# mod_mixer_v0_3_1.net
KiCad netlist of a schematic drawn in EAGLE
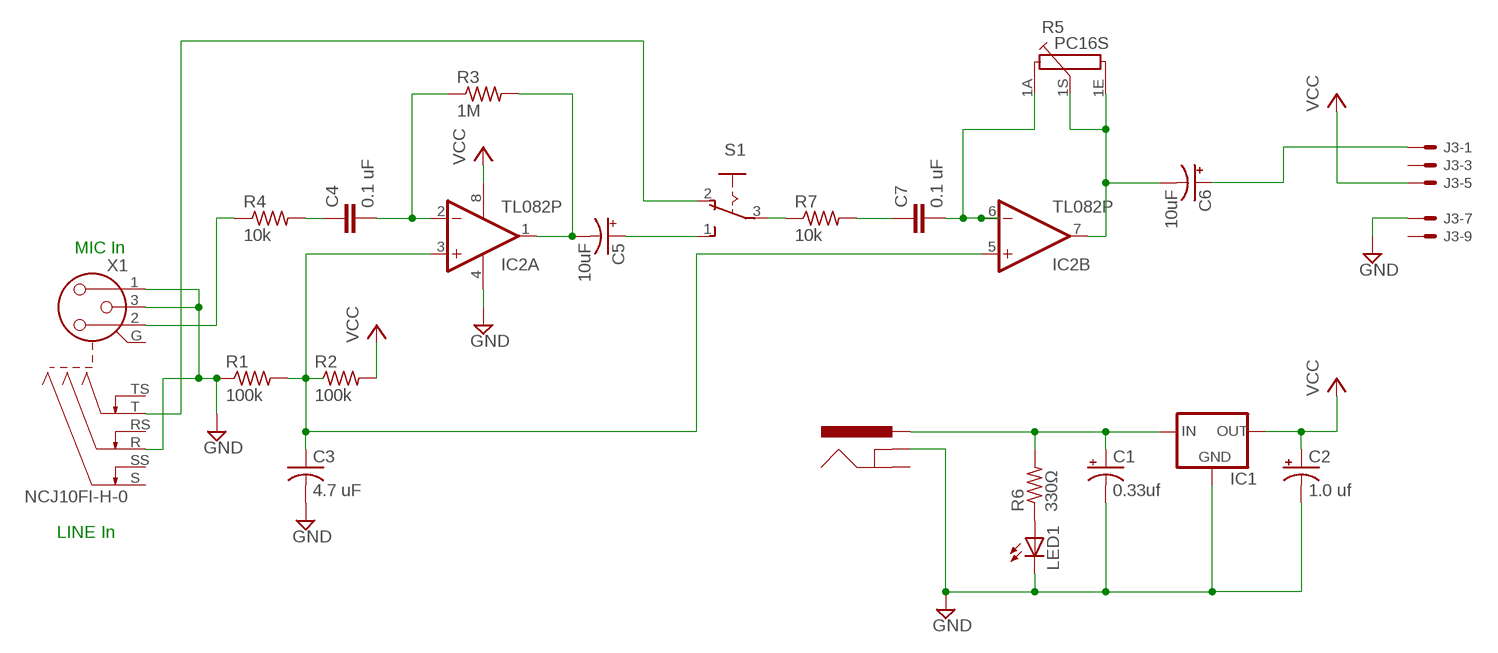
[diagram p0: schematic, sheet 1]

(export (version "E")
  (design (tool "Eeschema 10.0.6"))
  (components
    (comp (ref "C1")
      (value "0.33uf")
      (footprint "eagle-import:E2,5-6")
      (libsource (lib "eagle-import") (part "CPOL-USE2.5-6"))
    )
    (comp (ref "C2")
      (value "1.0 uf")
      (footprint "eagle-import:E2,5-6")
      (libsource (lib "eagle-import") (part "CPOL-USE2.5-6"))
    )
    (comp (ref "C3")
      (value "4.7 uF")
      (footprint "eagle-import:C050-030X075")
      (libsource (lib "eagle-import") (part "C-US050-030X075"))
    )
    (comp (ref "C4")
      (value "0.1 uF")
      (footprint "eagle-import:C5B2.5")
      (libsource (lib "eagle-import") (part "C5/2.5"))
    )
    (comp (ref "C5")
      (value "10uF")
      (footprint "eagle-import:E5-6")
      (libsource (lib "eagle-import") (part "CPOL-USE5-6"))
    )
    (comp (ref "C6")
      (value "10uF")
      (footprint "eagle-import:E2,5-7")
      (libsource (lib "eagle-import") (part "CPOL-USE2.5-7"))
    )
    (comp (ref "C7")
      (value "0.1 uF")
      (footprint "eagle-import:C5B2.5")
      (libsource (lib "eagle-import") (part "C5/2.5"))
    )
    (comp (ref "IC1")
      (value "V_REG_78XXSIDE")
      (footprint "eagle-import:78XXL")
      (libsource (lib "eagle-import") (part "V_REG_78XXSIDE"))
    )
    (comp (ref "IC2")
      (value "TL082P")
      (footprint "eagle-import:DIL08")
      (libsource (lib "eagle-import") (part "TL082P"))
    )
    (comp (ref "J1")
      (value "POWER_JACKSLT")
      (footprint "eagle-import:POWER_JACK_SLOT")
      (libsource (lib "eagle-import") (part "POWER_JACKSLT"))
    )
    (comp (ref "J3")
      (value "CON-50-EDGE")
      (footprint "eagle-import:CARDEDGE-50")
      (libsource (lib "eagle-import") (part "CON-50-EDGE"))
    )
    (comp (ref "LED1")
      (value "LEDSFH480")
      (footprint "eagle-import:SFH480")
      (libsource (lib "eagle-import") (part "LEDSFH480"))
    )
    (comp (ref "R1")
      (value "100k")
      (footprint "eagle-import:0207_10")
      (libsource (lib "eagle-import") (part "R-US_0207/10"))
    )
    (comp (ref "R2")
      (value "100k")
      (footprint "eagle-import:0207_10")
      (libsource (lib "eagle-import") (part "R-US_0207/10"))
    )
    (comp (ref "R3")
      (value "1M")
      (footprint "eagle-import:0207_10")
      (libsource (lib "eagle-import") (part "R-US_0207/10"))
    )
    (comp (ref "R4")
      (value "10k")
      (footprint "eagle-import:0207_10")
      (libsource (lib "eagle-import") (part "R-US_0207/10"))
    )
    (comp (ref "R5")
      (value "PC16S")
      (footprint "eagle-import:PC16S")
      (libsource (lib "eagle-import") (part "PC16S"))
    )
    (comp (ref "R6")
      (value "330Ω")
      (footprint "eagle-import:0207_10")
      (libsource (lib "eagle-import") (part "R-US_0207/10"))
    )
    (comp (ref "R7")
      (value "10k")
      (footprint "eagle-import:0207_10")
      (libsource (lib "eagle-import") (part "R-US_0207/10"))
    )
    (comp (ref "S1")
      (value "255SB")
      (footprint "eagle-import:255SB")
      (libsource (lib "eagle-import") (part "255SB"))
    )
    (comp (ref "X1")
      (value "NCJ10FI-H-0")
      (footprint "eagle-import:NCJ10FI-H-0")
      (libsource (lib "eagle-import") (part "NCJ10FI-H-0"))
    )
  )
  (nets
    (net (code "1") (name "GND") (class "Default")
      (node (ref "C1") (pin "-") (pinfunction "-_-") (pintype "passive"))
      (node (ref "C2") (pin "-") (pinfunction "-_-") (pintype "passive"))
      (node (ref "C3") (pin "2") (pinfunction "2_2") (pintype "passive"))
      (node (ref "IC1") (pin "GND") (pinfunction "GND_GND") (pintype "input"))
      (node (ref "IC2") (pin "4") (pinfunction "V-_4") (pintype "power_in"))
      (node (ref "J1") (pin "GND@1") (pinfunction "GNDBREAK_GND@1") (pintype "bidirectional"))
      (node (ref "J3") (pin "7") (pinfunction "S_7") (pintype "passive"))
      (node (ref "LED1") (pin "K") (pinfunction "C_K") (pintype "passive"))
      (node (ref "R1") (pin "1") (pinfunction "1_1") (pintype "passive"))
      (node (ref "X1") (pin "1") (pinfunction "1_1") (pintype "passive"))
      (node (ref "X1") (pin "3") (pinfunction "3_3") (pintype "passive"))
      (node (ref "X1") (pin "R") (pinfunction "R_R") (pintype "passive"))
    )
    (net (code "2") (name "Net-(C1-Pad+)") (class "Default")
      (node (ref "C1") (pin "+") (pinfunction "+_+") (pintype "passive"))
      (node (ref "IC1") (pin "IN") (pinfunction "IN_IN") (pintype "input"))
      (node (ref "J1") (pin "PWR") (pinfunction "PWR_PWR") (pintype "bidirectional"))
      (node (ref "R6") (pin "2") (pinfunction "2_2") (pintype "passive"))
    )
    (net (code "3") (name "Net-(C4-Pad1)") (class "Default")
      (node (ref "C4") (pin "1") (pinfunction "1_1") (pintype "passive"))
      (node (ref "R4") (pin "2") (pinfunction "2_2") (pintype "passive"))
    )
    (net (code "4") (name "Net-(C7-Pad1)") (class "Default")
      (node (ref "C7") (pin "1") (pinfunction "1_1") (pintype "passive"))
      (node (ref "R7") (pin "2") (pinfunction "2_2") (pintype "passive"))
    )
    (net (code "5") (name "Net-(IC2A-+IN)") (class "Default")
      (node (ref "C3") (pin "1") (pinfunction "1_1") (pintype "passive"))
      (node (ref "IC2") (pin "3") (pinfunction "+IN_3") (pintype "input"))
      (node (ref "IC2") (pin "5") (pinfunction "+IN_5") (pintype "input"))
      (node (ref "R1") (pin "2") (pinfunction "2_2") (pintype "passive"))
      (node (ref "R2") (pin "1") (pinfunction "1_1") (pintype "passive"))
    )
    (net (code "6") (name "Net-(IC2A--IN)") (class "Default")
      (node (ref "C4") (pin "2") (pinfunction "2_2") (pintype "passive"))
      (node (ref "IC2") (pin "2") (pinfunction "-IN_2") (pintype "input"))
      (node (ref "R3") (pin "1") (pinfunction "1_1") (pintype "passive"))
    )
    (net (code "7") (name "Net-(IC2A-OUT)") (class "Default")
      (node (ref "C5") (pin "-") (pinfunction "-_-") (pintype "passive"))
      (node (ref "IC2") (pin "1") (pinfunction "OUT_1") (pintype "output"))
      (node (ref "R3") (pin "2") (pinfunction "2_2") (pintype "passive"))
    )
    (net (code "8") (name "Net-(IC2B--IN)") (class "Default")
      (node (ref "C7") (pin "2") (pinfunction "2_2") (pintype "passive"))
      (node (ref "IC2") (pin "6") (pinfunction "-IN_6") (pintype "input"))
      (node (ref "R5") (pin "1A") (pinfunction "1A_1A") (pintype "passive"))
    )
    (net (code "9") (name "Net-(IC2B-OUT)") (class "Default")
      (node (ref "C6") (pin "-") (pinfunction "-_-") (pintype "passive"))
      (node (ref "IC2") (pin "7") (pinfunction "OUT_7") (pintype "output"))
      (node (ref "R5") (pin "1E") (pinfunction "1E_1E") (pintype "passive"))
      (node (ref "R5") (pin "1S") (pinfunction "1S_1S") (pintype "passive"))
    )
    (net (code "10") (name "Net-(J3A-S)") (class "Default")
      (node (ref "C6") (pin "+") (pinfunction "+_+") (pintype "passive"))
      (node (ref "J3") (pin "1") (pinfunction "S_1") (pintype "passive"))
    )
    (net (code "11") (name "Net-(LED1-PadA)") (class "Default")
      (node (ref "LED1") (pin "A") (pinfunction "A_A") (pintype "passive"))
      (node (ref "R6") (pin "1") (pinfunction "1_1") (pintype "passive"))
    )
    (net (code "12") (name "Net-(R4-Pad1)") (class "Default")
      (node (ref "R4") (pin "1") (pinfunction "1_1") (pintype "passive"))
      (node (ref "X1") (pin "2") (pinfunction "2_2") (pintype "passive"))
    )
    (net (code "13") (name "Net-(S1-O)") (class "Default")
      (node (ref "S1") (pin "2") (pinfunction "O_2") (pintype "passive"))
      (node (ref "X1") (pin "T") (pinfunction "T_T") (pintype "passive"))
    )
    (net (code "14") (name "Net-(S1-P)") (class "Default")
      (node (ref "R7") (pin "1") (pinfunction "1_1") (pintype "passive"))
      (node (ref "S1") (pin "3") (pinfunction "P_3") (pintype "passive"))
    )
    (net (code "15") (name "Net-(S1-S)") (class "Default")
      (node (ref "C5") (pin "+") (pinfunction "+_+") (pintype "passive"))
      (node (ref "S1") (pin "1") (pinfunction "S_1") (pintype "passive"))
    )
    (net (code "16") (name "VCC") (class "Default")
      (node (ref "C2") (pin "+") (pinfunction "+_+") (pintype "passive"))
      (node (ref "IC1") (pin "OUT") (pinfunction "OUT_OUT") (pintype "output"))
      (node (ref "IC2") (pin "8") (pinfunction "V+_8") (pintype "power_in"))
      (node (ref "J3") (pin "5") (pinfunction "S_5") (pintype "passive"))
      (node (ref "R2") (pin "2") (pinfunction "2_2") (pintype "passive"))
    )
    (net (code "17") (name "unconnected-(J1-GND-PadGND@2)") (class "Default")
      (node (ref "J1") (pin "GND@2") (pinfunction "GND_GND@2") (pintype "bidirectional"))
    )
    (net (code "18") (name "unconnected-(J3B-S-Pad3)") (class "Default")
      (node (ref "J3") (pin "3") (pinfunction "S_3") (pintype "passive"))
    )
    (net (code "19") (name "unconnected-(J3E-S-Pad9)") (class "Default")
      (node (ref "J3") (pin "9") (pinfunction "S_9") (pintype "passive"))
    )
    (net (code "20") (name "unconnected-(X1-PadG)") (class "Default")
      (node (ref "X1") (pin "G") (pinfunction "G_G") (pintype "passive"))
    )
    (net (code "21") (name "unconnected-(X1-PadRS)") (class "Default")
      (node (ref "X1") (pin "RS") (pinfunction "RS_RS") (pintype "passive"))
    )
    (net (code "22") (name "unconnected-(X1-PadS)") (class "Default")
      (node (ref "X1") (pin "S") (pinfunction "S_S") (pintype "passive"))
    )
    (net (code "23") (name "unconnected-(X1-PadSS)") (class "Default")
      (node (ref "X1") (pin "SS") (pinfunction "SS_SS") (pintype "passive"))
    )
    (net (code "24") (name "unconnected-(X1-PadTS)") (class "Default")
      (node (ref "X1") (pin "TS") (pinfunction "TS_TS") (pintype "passive"))
    )
  )
)
